# Roseta_Shield.net
KiCad netlist of a schematic drawn in Altium Designer
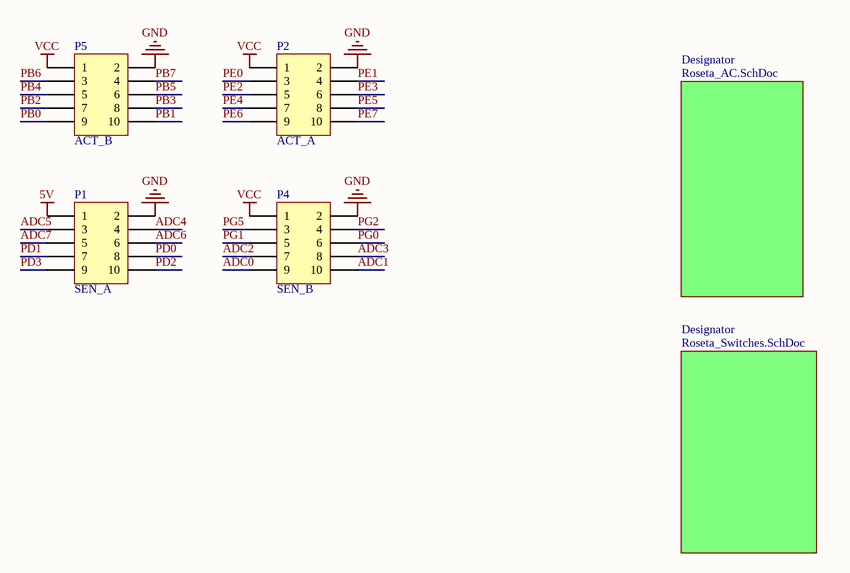
[diagram p0: Roseta_Shield.SchDoc]

(export (version "E")
  (design (tool "Eeschema 10.0.6"))
  (components
    (comp (ref "P1")
      (value "SEN_A")
      (footprint "HDR2X5_Female_Slim")
      (description "Header, 5-Pin, Dual row")
      (fields (field (name "PUBLISHER") "Altium Limited"))
      (libsource (lib "Miscellaneous Connectors") (part "Header 5X2"))
    )
    (comp (ref "P2")
      (value "ACT_A")
      (footprint "HDR2X5_Female_Slim")
      (description "Header, 5-Pin, Dual row")
      (fields (field (name "PUBLISHER") "Altium Limited"))
      (libsource (lib "Miscellaneous Connectors") (part "Header 5X2"))
    )
    (comp (ref "P4")
      (value "SEN_B")
      (footprint "HDR2X5_Female_Slim")
      (description "Header, 5-Pin, Dual row")
      (fields (field (name "PUBLISHER") "Altium Limited"))
      (libsource (lib "Miscellaneous Connectors") (part "Header 5X2"))
    )
    (comp (ref "P5")
      (value "ACT_B")
      (footprint "HDR2X5_Female_Slim")
      (description "Header, 5-Pin, Dual row")
      (fields (field (name "PUBLISHER") "Altium Limited"))
      (libsource (lib "Miscellaneous Connectors") (part "Header 5X2"))
    )
  )
  (nets
    (net (code "1") (name "/ADC0") (class "Default")
      (node (ref "P4") (pin "9") (pinfunction "9_9") (pintype "passive"))
    )
    (net (code "2") (name "/ADC1") (class "Default")
      (node (ref "P4") (pin "10") (pinfunction "10_10") (pintype "passive"))
    )
    (net (code "3") (name "/ADC2") (class "Default")
      (node (ref "P4") (pin "7") (pinfunction "7_7") (pintype "passive"))
    )
    (net (code "4") (name "/ADC3") (class "Default")
      (node (ref "P4") (pin "8") (pinfunction "8_8") (pintype "passive"))
    )
    (net (code "5") (name "/ADC4") (class "Default")
      (node (ref "P1") (pin "4") (pinfunction "4_4") (pintype "passive"))
    )
    (net (code "6") (name "/ADC5") (class "Default")
      (node (ref "P1") (pin "3") (pinfunction "3_3") (pintype "passive"))
    )
    (net (code "7") (name "/ADC6") (class "Default")
      (node (ref "P1") (pin "6") (pinfunction "6_6") (pintype "passive"))
    )
    (net (code "8") (name "/ADC7") (class "Default")
      (node (ref "P1") (pin "5") (pinfunction "5_5") (pintype "passive"))
    )
    (net (code "9") (name "/PB0") (class "Default")
      (node (ref "P5") (pin "9") (pinfunction "9_9") (pintype "passive"))
    )
    (net (code "10") (name "/PB1") (class "Default")
      (node (ref "P5") (pin "10") (pinfunction "10_10") (pintype "passive"))
    )
    (net (code "11") (name "/PB2") (class "Default")
      (node (ref "P5") (pin "7") (pinfunction "7_7") (pintype "passive"))
    )
    (net (code "12") (name "/PB3") (class "Default")
      (node (ref "P5") (pin "8") (pinfunction "8_8") (pintype "passive"))
    )
    (net (code "13") (name "/PB4") (class "Default")
      (node (ref "P5") (pin "5") (pinfunction "5_5") (pintype "passive"))
    )
    (net (code "14") (name "/PB5") (class "Default")
      (node (ref "P5") (pin "6") (pinfunction "6_6") (pintype "passive"))
    )
    (net (code "15") (name "/PB6") (class "Default")
      (node (ref "P5") (pin "3") (pinfunction "3_3") (pintype "passive"))
    )
    (net (code "16") (name "/PB7") (class "Default")
      (node (ref "P5") (pin "4") (pinfunction "4_4") (pintype "passive"))
    )
    (net (code "17") (name "/PD0") (class "Default")
      (node (ref "P1") (pin "8") (pinfunction "8_8") (pintype "passive"))
    )
    (net (code "18") (name "/PD1") (class "Default")
      (node (ref "P1") (pin "7") (pinfunction "7_7") (pintype "passive"))
    )
    (net (code "19") (name "/PD2") (class "Default")
      (node (ref "P1") (pin "10") (pinfunction "10_10") (pintype "passive"))
    )
    (net (code "20") (name "/PD3") (class "Default")
      (node (ref "P1") (pin "9") (pinfunction "9_9") (pintype "passive"))
    )
    (net (code "21") (name "/PE0") (class "Default")
      (node (ref "P2") (pin "3") (pinfunction "3_3") (pintype "passive"))
    )
    (net (code "22") (name "/PE1") (class "Default")
      (node (ref "P2") (pin "4") (pinfunction "4_4") (pintype "passive"))
    )
    (net (code "23") (name "/PE2") (class "Default")
      (node (ref "P2") (pin "5") (pinfunction "5_5") (pintype "passive"))
    )
    (net (code "24") (name "/PE3") (class "Default")
      (node (ref "P2") (pin "6") (pinfunction "6_6") (pintype "passive"))
    )
    (net (code "25") (name "/PE4") (class "Default")
      (node (ref "P2") (pin "7") (pinfunction "7_7") (pintype "passive"))
    )
    (net (code "26") (name "/PE5") (class "Default")
      (node (ref "P2") (pin "8") (pinfunction "8_8") (pintype "passive"))
    )
    (net (code "27") (name "/PE6") (class "Default")
      (node (ref "P2") (pin "9") (pinfunction "9_9") (pintype "passive"))
    )
    (net (code "28") (name "/PE7") (class "Default")
      (node (ref "P2") (pin "10") (pinfunction "10_10") (pintype "passive"))
    )
    (net (code "29") (name "/PG0") (class "Default")
      (node (ref "P4") (pin "6") (pinfunction "6_6") (pintype "passive"))
    )
    (net (code "30") (name "/PG1") (class "Default")
      (node (ref "P4") (pin "5") (pinfunction "5_5") (pintype "passive"))
    )
    (net (code "31") (name "/PG2") (class "Default")
      (node (ref "P4") (pin "4") (pinfunction "4_4") (pintype "passive"))
    )
    (net (code "32") (name "/PG5") (class "Default")
      (node (ref "P4") (pin "3") (pinfunction "3_3") (pintype "passive"))
    )
    (net (code "33") (name "5V") (class "Default")
      (node (ref "P1") (pin "1") (pinfunction "1_1") (pintype "passive"))
    )
    (net (code "34") (name "GND") (class "Default")
      (node (ref "P1") (pin "2") (pinfunction "2_2") (pintype "passive"))
      (node (ref "P2") (pin "2") (pinfunction "2_2") (pintype "passive"))
      (node (ref "P4") (pin "2") (pinfunction "2_2") (pintype "passive"))
      (node (ref "P5") (pin "2") (pinfunction "2_2") (pintype "passive"))
    )
    (net (code "35") (name "VCC") (class "Default")
      (node (ref "P2") (pin "1") (pinfunction "1_1") (pintype "passive"))
      (node (ref "P4") (pin "1") (pinfunction "1_1") (pintype "passive"))
      (node (ref "P5") (pin "1") (pinfunction "1_1") (pintype "passive"))
    )
  )
)
